# balancing.net
KiCad netlist of a schematic drawn in Altium Designer
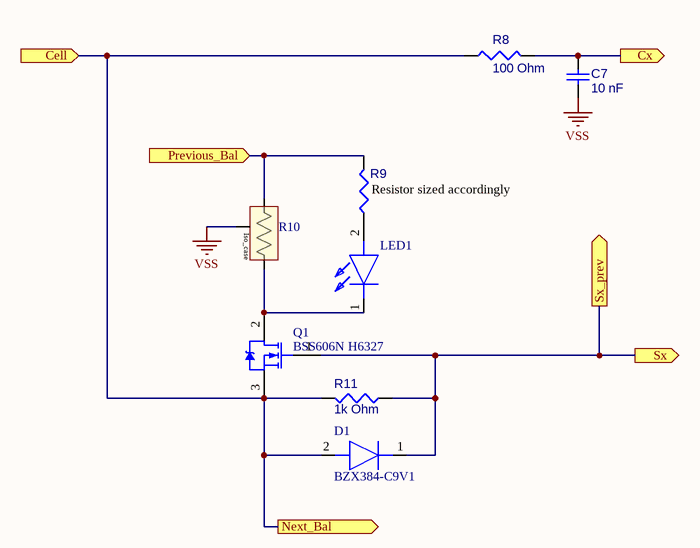
[diagram p0: balancing.SchDoc]

(export (version "E")
  (design (tool "Eeschema 10.0.6"))
  (components
    (comp (ref "C7")
      (value "10 nF")
      (footprint "CAPC2012X14M")
      (description "0805_generic_capacitor")
      (libsource (lib "EMEA - University of Patras - UP Karting") (part "Copy of CAP-NP-2"))
    )
    (comp (ref "D1")
      (value "BZX384-C9V1")
      (footprint "SamacSys:SOD2512X110N")
      (description "Diode")
      (libsource (lib "*") (part "BZX384-C9V1"))
    )
    (comp (ref "LED1")
      (value "LS_R976-NR-1")
      (footprint "SamacSys:LEDC2012X40N")
      (description "LED")
      (fields
        (field (name "MANUFACTURER_PART_NUMBER") "LS R976-NR-1")
        (field (name "MOUSER PART NUMBER") "720-LSR976-NR-1")
      )
      (libsource (lib "*") (part "LS_R976-NR-1"))
    )
    (comp (ref "Q1")
      (value "BSS606N H6327")
      (footprint "INF-PG-SOT-89_N")
      (description "OptiMOS-3 Small-Signal-Transistor, 60 V VDS, 3.2 A ID, PG-SOT-89, Reel, Green")
      (fields (field (name "MANUFACTURER") "Infineon"))
      (libsource (lib "Altium Content Vault") (part "INF-BSS606NH6327-PG-SOT-89-4"))
    )
    (comp (ref "R8")
      (value "100 Ohm")
      (footprint "RESC2012X06M")
      (description "805_generic_resistor")
      (libsource (lib "EMEA - University of Patras - UP Karting") (part "RES-2"))
    )
    (comp (ref "R9")
      (value "~")
      (footprint "RESC2012X06M")
      (description "805_generic_resistor")
      (libsource (lib "EMEA - University of Patras - UP Karting") (part "RES-2"))
    )
    (comp (ref "R10")
      (value "DTO025C2R200JTE3")
      (footprint "RES_DTO025_VIS-M")
      (description "Description")
      (fields (field (name "COPYRIGHT") "Copyright (C) 2026 Ultra Librarian. All rights reserved."))
      (libsource (lib "EMEA - University of Patras - UP Karting") (part "DTO025C2R200JTE3"))
    )
    (comp (ref "R11")
      (value "1k Ohm")
      (footprint "RESC2012X06M")
      (description "805_generic_resistor")
      (libsource (lib "EMEA - University of Patras - UP Karting") (part "RES-2"))
    )
  )
  (nets
    (net (code "1") (name "/Cell") (class "Default")
      (node (ref "D1") (pin "2") (pinfunction "A_2") (pintype "passive"))
      (node (ref "Q1") (pin "3") (pinfunction "S_3") (pintype "passive"))
      (node (ref "R11") (pin "2") (pinfunction "2_2") (pintype "passive"))
      (node (ref "R8") (pin "1") (pinfunction "1_1") (pintype "passive"))
    )
    (net (code "2") (name "/Cx") (class "Default")
      (node (ref "C7") (pin "1") (pinfunction "1_1") (pintype "passive"))
      (node (ref "R8") (pin "2") (pinfunction "2_2") (pintype "passive"))
    )
    (net (code "3") (name "/Previous_Bal") (class "Default")
      (node (ref "R10") (pin "2") (pinfunction "2_2") (pintype "passive"))
      (node (ref "R9") (pin "2") (pinfunction "2_2") (pintype "passive"))
    )
    (net (code "4") (name "/Sx") (class "Default")
      (node (ref "D1") (pin "1") (pinfunction "K_1") (pintype "passive"))
      (node (ref "Q1") (pin "1") (pinfunction "G_1") (pintype "passive"))
      (node (ref "R11") (pin "1") (pinfunction "1_1") (pintype "passive"))
    )
    (net (code "5") (name "Net-(LED1-A)") (class "Default")
      (node (ref "LED1") (pin "2") (pinfunction "A_2") (pintype "passive"))
      (node (ref "R9") (pin "1") (pinfunction "1_1") (pintype "passive"))
    )
    (net (code "6") (name "Net-(LED1-K)") (class "Default")
      (node (ref "LED1") (pin "1") (pinfunction "K_1") (pintype "passive"))
      (node (ref "Q1") (pin "2") (pinfunction "D_2") (pintype "passive"))
      (node (ref "R10") (pin "1") (pinfunction "1_1") (pintype "passive"))
    )
    (net (code "7") (name "VSS") (class "Default")
      (node (ref "C7") (pin "2") (pinfunction "2_2") (pintype "passive"))
      (node (ref "R10") (pin "3") (pinfunction "3_3") (pintype "passive"))
    )
  )
)
